# HUM_SENS.net
KiCad netlist of a schematic drawn in Altium Designer
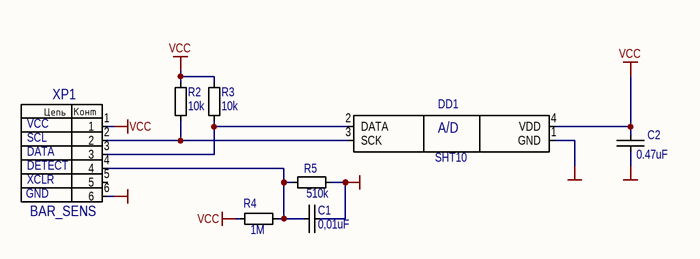
[diagram p0: HUM_SENS.SchDoc]

(export (version "E")
  (design (tool "Eeschema 10.0.6"))
  (components
    (comp (ref "C1")
      (value "0,01uF")
      (footprint "Cap_0805")
      (fields (field (name "MANUFACTURER") "AVX") (field (name "PART NUMBER") "08055C103JAT2A"))
      (libsource (lib "PANEL") (part "Cap_0805"))
    )
    (comp (ref "C2")
      (value "0.47uF")
      (footprint "Cap_0805")
      (fields (field (name "MANUFACTURER") "AVX") (field (name "PART NUMBER") "0805YC475KAT2A"))
      (libsource (lib "PANEL") (part "Cap_0805"))
    )
    (comp (ref "DD1") (value "SHT10") (footprint "SHT10") (libsource (lib "HUM_SENS") (part "SHT10")))
    (comp (ref "R2")
      (value "10k")
      (footprint "Res_0805")
      (fields (field (name "MANUFACTURER") "Vishay"))
      (libsource (lib "PANEL") (part "Res_0805"))
    )
    (comp (ref "R3")
      (value "10k")
      (footprint "Res_0805")
      (fields (field (name "MANUFACTURER") "Vishay"))
      (libsource (lib "PANEL") (part "Res_0805"))
    )
    (comp (ref "R4")
      (value "1M")
      (footprint "Res_0805")
      (fields (field (name "MANUFACTURER") "Vishay"))
      (libsource (lib "") (part "Res_0805_1"))
    )
    (comp (ref "R5")
      (value "510k")
      (footprint "Res_0805")
      (fields (field (name "MANUFACTURER") "Vishay"))
      (libsource (lib "") (part "Res_0805_1"))
    )
    (comp (ref "XP1")
      (value "BAR_SENS")
      (footprint "SENS_LEGS")
      (libsource (lib "BAR_SENS") (part "BAR_SENS"))
    )
  )
  (nets
    (net (code "1") (name "GND") (class "Default")
      (node (ref "C1") (pin "2") (pinfunction "2_2") (pintype "passive"))
      (node (ref "C2") (pin "1") (pinfunction "1_1") (pintype "passive"))
      (node (ref "DD1") (pin "1") (pinfunction "GND_1") (pintype "passive"))
      (node (ref "R5") (pin "1") (pinfunction "1_1") (pintype "passive"))
      (node (ref "XP1") (pin "6") (pinfunction "6_6") (pintype "passive"))
    )
    (net (code "2") (name "Net-(C1-Pad1)") (class "Default")
      (node (ref "C1") (pin "1") (pinfunction "1_1") (pintype "passive"))
      (node (ref "R4") (pin "1") (pinfunction "1_1") (pintype "passive"))
      (node (ref "R5") (pin "2") (pinfunction "2_2") (pintype "passive"))
      (node (ref "XP1") (pin "4") (pinfunction "4_4") (pintype "passive"))
    )
    (net (code "3") (name "Net-(DD1-DATA)") (class "Default")
      (node (ref "DD1") (pin "2") (pinfunction "DATA_2") (pintype "passive"))
      (node (ref "R3") (pin "2") (pinfunction "2_2") (pintype "passive"))
      (node (ref "XP1") (pin "3") (pinfunction "3_3") (pintype "passive"))
    )
    (net (code "4") (name "Net-(DD1-SCK)") (class "Default")
      (node (ref "DD1") (pin "3") (pinfunction "SCK_3") (pintype "passive"))
      (node (ref "R2") (pin "2") (pinfunction "2_2") (pintype "passive"))
      (node (ref "XP1") (pin "2") (pinfunction "2_2") (pintype "passive"))
    )
    (net (code "5") (name "VCC") (class "Default")
      (node (ref "C2") (pin "2") (pinfunction "2_2") (pintype "passive"))
      (node (ref "DD1") (pin "4") (pinfunction "VDD_4") (pintype "passive"))
      (node (ref "R2") (pin "1") (pinfunction "1_1") (pintype "passive"))
      (node (ref "R3") (pin "1") (pinfunction "1_1") (pintype "passive"))
      (node (ref "R4") (pin "2") (pinfunction "2_2") (pintype "passive"))
      (node (ref "XP1") (pin "1") (pinfunction "1_1") (pintype "passive"))
    )
    (net (code "6") (name "unconnected-(XP1-Pad5)") (class "Default")
      (node (ref "XP1") (pin "5") (pinfunction "5_5") (pintype "passive"))
    )
  )
)
